# TKX90001_-_STRATASYS.net
KiCad netlist of a schematic drawn in EAGLE
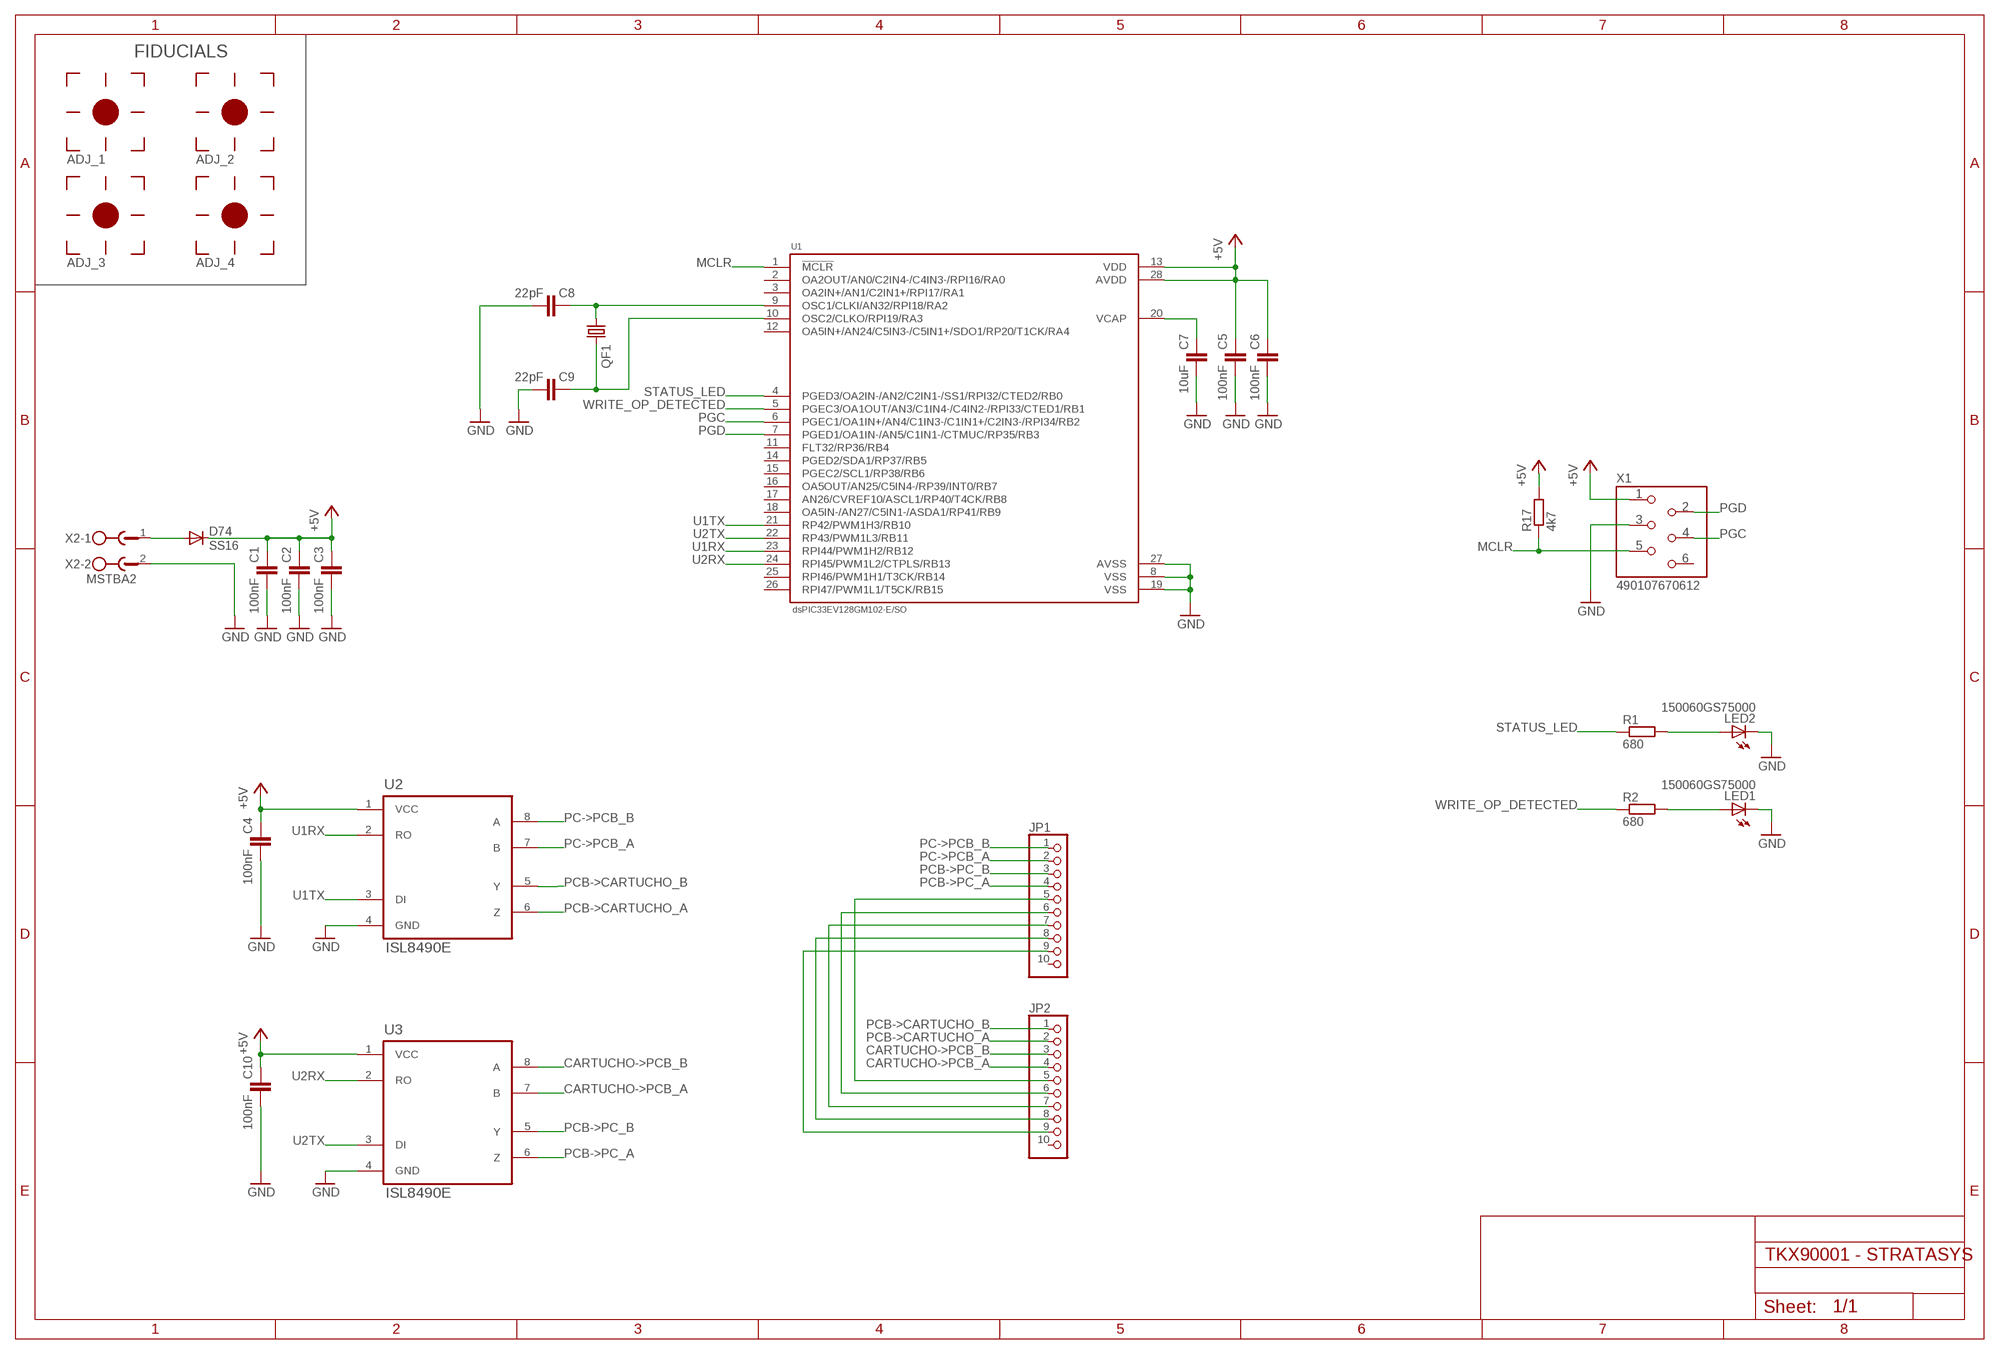
[diagram p0: schematic, sheet 1]

(export (version "E")
  (design (tool "Eeschema 10.0.6"))
  (components
    (comp (ref "ADJ_1")
      (value "FIDUCIAL")
      (footprint "eagle-import:FIDUCIAL")
      (libsource (lib "eagle-import") (part "FIDUCIAL"))
    )
    (comp (ref "ADJ_2")
      (value "FIDUCIAL")
      (footprint "eagle-import:FIDUCIAL")
      (libsource (lib "eagle-import") (part "FIDUCIAL"))
    )
    (comp (ref "ADJ_3")
      (value "FIDUCIAL")
      (footprint "eagle-import:FIDUCIAL")
      (libsource (lib "eagle-import") (part "FIDUCIAL"))
    )
    (comp (ref "ADJ_4")
      (value "FIDUCIAL")
      (footprint "eagle-import:FIDUCIAL")
      (libsource (lib "eagle-import") (part "FIDUCIAL"))
    )
    (comp (ref "C1")
      (value "100nF")
      (footprint "eagle-import:C0603K")
      (fields (field (name "PARTNO") "885012206020"))
      (libsource (lib "eagle-import") (part "C-EUC0603K"))
    )
    (comp (ref "C2")
      (value "100nF")
      (footprint "eagle-import:C0603K")
      (fields (field (name "PARTNO") "885012206020"))
      (libsource (lib "eagle-import") (part "C-EUC0603K"))
    )
    (comp (ref "C3")
      (value "100nF")
      (footprint "eagle-import:C0603K")
      (fields (field (name "PARTNO") "885012206020"))
      (libsource (lib "eagle-import") (part "C-EUC0603K"))
    )
    (comp (ref "C4")
      (value "100nF")
      (footprint "eagle-import:C0603K")
      (fields (field (name "PARTNO") "885012206020"))
      (libsource (lib "eagle-import") (part "C-EUC0603K"))
    )
    (comp (ref "C5")
      (value "100nF")
      (footprint "eagle-import:C0603K")
      (fields (field (name "PARTNO") "885012206020"))
      (libsource (lib "eagle-import") (part "C-EUC0603K"))
    )
    (comp (ref "C6")
      (value "100nF")
      (footprint "eagle-import:C0603K")
      (fields (field (name "PARTNO") "885012206020"))
      (libsource (lib "eagle-import") (part "C-EUC0603K"))
    )
    (comp (ref "C7")
      (value "10uF")
      (footprint "eagle-import:C1206K")
      (fields (field (name "PARTNO") "TAJA106K016RNJV"))
      (libsource (lib "eagle-import") (part "rcl_334_C-EUC1206K"))
    )
    (comp (ref "C8")
      (value "22pF")
      (footprint "eagle-import:C0603K")
      (fields (field (name "PARTNO") "C0603C220M4RACAUTO"))
      (libsource (lib "eagle-import") (part "rcl_334_C-EUC0603K"))
    )
    (comp (ref "C9")
      (value "22pF")
      (footprint "eagle-import:C0603K")
      (fields (field (name "PARTNO") "C0603C220M4RACAUTO"))
      (libsource (lib "eagle-import") (part "C-EUC0603K"))
    )
    (comp (ref "C10")
      (value "100nF")
      (footprint "eagle-import:C0603K")
      (fields (field (name "PARTNO") "885012206020"))
      (libsource (lib "eagle-import") (part "C-EUC0603K"))
    )
    (comp (ref "D74")
      (value "SS16")
      (footprint "eagle-import:SMB")
      (fields (field (name "PARTNO") "SS16T3G"))
      (libsource (lib "eagle-import") (part "DIODE-SMB"))
    )
    (comp (ref "JP1")
      (value "PINHD-1X10/90")
      (footprint "eagle-import:1X10_90")
      (libsource (lib "eagle-import") (part "PINHD-1X10/90"))
    )
    (comp (ref "JP2")
      (value "PINHD-1X10/90")
      (footprint "eagle-import:1X10_90")
      (libsource (lib "eagle-import") (part "PINHD-1X10/90"))
    )
    (comp (ref "LED1")
      (value "150060GS75000")
      (footprint "eagle-import:SML0603")
      (libsource (lib "eagle-import") (part "LEDSML0603"))
    )
    (comp (ref "LED2")
      (value "150060GS75000")
      (footprint "eagle-import:SML0603")
      (libsource (lib "eagle-import") (part "LEDSML0603"))
    )
    (comp (ref "QF1")
      (value "CRYSTALHC49S")
      (footprint "eagle-import:HC49_S")
      (libsource (lib "eagle-import") (part "CRYSTALHC49S"))
    )
    (comp (ref "R1")
      (value "680")
      (footprint "eagle-import:R0603")
      (fields (field (name "PARTNO") "RC0603FR-13680RL"))
      (libsource (lib "eagle-import") (part "R-EU_R0603"))
    )
    (comp (ref "R2")
      (value "680")
      (footprint "eagle-import:R0603")
      (fields (field (name "PARTNO") "RC0603FR-13680RL"))
      (libsource (lib "eagle-import") (part "R-EU_R0603"))
    )
    (comp (ref "R17")
      (value "4k7")
      (footprint "eagle-import:R0603")
      (fields (field (name "PARTNO") "RC0603FR-074K7L"))
      (libsource (lib "eagle-import") (part "R-EU_R0603"))
    )
    (comp (ref "U1")
      (value "dsPIC33EV128GM102-E/SO")
      (footprint "eagle-import:SOIC127P1028X256-28N")
      (fields (field (name "PARTNO") " dsPIC33EV128GM102-E/SO"))
      (libsource (lib "eagle-import") (part "DSPIC33EV128GM104-E/PT"))
    )
    (comp (ref "U2")
      (value "ISL8490E")
      (footprint "eagle-import:SOIC127P600X175-8N")
      (fields (field (name "PARTNO") "ISL8490EIBZ"))
      (libsource (lib "eagle-import") (part "ISL8490E"))
    )
    (comp (ref "U3")
      (value "ISL8490E")
      (footprint "eagle-import:SOIC127P600X175-8N")
      (fields (field (name "PARTNO") "ISL8490EIBZ"))
      (libsource (lib "eagle-import") (part "ISL8490E"))
    )
    (comp (ref "X1")
      (value "490107670612")
      (footprint "eagle-import:REDFIT_6POS")
      (libsource (lib "eagle-import") (part "REDFIT_6POS"))
    )
    (comp (ref "X2")
      (value "MSTBA2")
      (footprint "eagle-import:MSTBA2")
      (fields (field (name "MF") "FARNELL") (field (name "MPN") "1757242") (field (name "DNP") "T"))
      (libsource (lib "eagle-import") (part "MSTBA2"))
    )
  )
  (nets
    (net (code "1") (name "+5V") (class "Default")
      (node (ref "C1") (pin "1") (pinfunction "1_1") (pintype "passive"))
      (node (ref "C10") (pin "1") (pinfunction "1_1") (pintype "passive"))
      (node (ref "C2") (pin "1") (pinfunction "1_1") (pintype "passive"))
      (node (ref "C3") (pin "1") (pinfunction "1_1") (pintype "passive"))
      (node (ref "C4") (pin "1") (pinfunction "1_1") (pintype "passive"))
      (node (ref "C5") (pin "1") (pinfunction "1_1") (pintype "passive"))
      (node (ref "C6") (pin "1") (pinfunction "1_1") (pintype "passive"))
      (node (ref "D74") (pin "C") (pinfunction "C_C") (pintype "passive"))
      (node (ref "R17") (pin "2") (pinfunction "2_2") (pintype "passive"))
      (node (ref "U1") (pin "13") (pinfunction "VDD_13") (pintype "power_in"))
      (node (ref "U1") (pin "28") (pinfunction "AVDD_28") (pintype "bidirectional"))
      (node (ref "U2") (pin "1") (pinfunction "VCC_1") (pintype "power_in"))
      (node (ref "U3") (pin "1") (pinfunction "VCC_1") (pintype "power_in"))
      (node (ref "X1") (pin "P$1") (pinfunction "P$1_P$1") (pintype "bidirectional"))
    )
    (net (code "2") (name "/CARTUCHO->PCB_A") (class "Default")
      (node (ref "JP2") (pin "4") (pinfunction "4_4") (pintype "passive"))
      (node (ref "U3") (pin "7") (pinfunction "B_7") (pintype "input"))
    )
    (net (code "3") (name "/CARTUCHO->PCB_B") (class "Default")
      (node (ref "JP2") (pin "3") (pinfunction "3_3") (pintype "passive"))
      (node (ref "U3") (pin "8") (pinfunction "A_8") (pintype "input"))
    )
    (net (code "4") (name "/MCLR") (class "Default")
      (node (ref "R17") (pin "1") (pinfunction "1_1") (pintype "passive"))
      (node (ref "U1") (pin "1") (pinfunction "~{MCLR}_1") (pintype "input"))
      (node (ref "X1") (pin "P$5") (pinfunction "P$5_P$5") (pintype "bidirectional"))
    )
    (net (code "5") (name "/PC->PCB_A") (class "Default")
      (node (ref "JP1") (pin "2") (pinfunction "2_2") (pintype "passive"))
      (node (ref "U2") (pin "7") (pinfunction "B_7") (pintype "input"))
    )
    (net (code "6") (name "/PC->PCB_B") (class "Default")
      (node (ref "JP1") (pin "1") (pinfunction "1_1") (pintype "passive"))
      (node (ref "U2") (pin "8") (pinfunction "A_8") (pintype "input"))
    )
    (net (code "7") (name "/PCB->CARTUCHO_A") (class "Default")
      (node (ref "JP2") (pin "2") (pinfunction "2_2") (pintype "passive"))
      (node (ref "U2") (pin "6") (pinfunction "Z_6") (pintype "output"))
    )
    (net (code "8") (name "/PCB->CARTUCHO_B") (class "Default")
      (node (ref "JP2") (pin "1") (pinfunction "1_1") (pintype "passive"))
      (node (ref "U2") (pin "5") (pinfunction "Y_5") (pintype "output"))
    )
    (net (code "9") (name "/PCB->PC_A") (class "Default")
      (node (ref "JP1") (pin "4") (pinfunction "4_4") (pintype "passive"))
      (node (ref "U3") (pin "6") (pinfunction "Z_6") (pintype "output"))
    )
    (net (code "10") (name "/PCB->PC_B") (class "Default")
      (node (ref "JP1") (pin "3") (pinfunction "3_3") (pintype "passive"))
      (node (ref "U3") (pin "5") (pinfunction "Y_5") (pintype "output"))
    )
    (net (code "11") (name "/PGC") (class "Default")
      (node (ref "U1") (pin "6") (pinfunction "PGEC1/OA1IN+/AN4/C1IN3-/C1IN1+/C2IN3-/RPI34/RB2_6") (pintype "bidirectional"))
      (node (ref "X1") (pin "P$4") (pinfunction "P$4_P$4") (pintype "bidirectional"))
    )
    (net (code "12") (name "/PGD") (class "Default")
      (node (ref "U1") (pin "7") (pinfunction "PGED1/OA1IN-/AN5/C1IN1-/CTMUC/RP35/RB3_7") (pintype "bidirectional"))
      (node (ref "X1") (pin "P$2") (pinfunction "P$2_P$2") (pintype "bidirectional"))
    )
    (net (code "13") (name "/STATUS_LED") (class "Default")
      (node (ref "R1") (pin "1") (pinfunction "1_1") (pintype "passive"))
      (node (ref "U1") (pin "4") (pinfunction "PGED3/OA2IN-/AN2/C2IN1-/SS1/RPI32/CTED2/RB0_4") (pintype "bidirectional"))
    )
    (net (code "14") (name "/U1RX") (class "Default")
      (node (ref "U1") (pin "23") (pinfunction "RPI44/PWM1H2/RB12_23") (pintype "bidirectional"))
      (node (ref "U2") (pin "2") (pinfunction "RO_2") (pintype "output"))
    )
    (net (code "15") (name "/U1TX") (class "Default")
      (node (ref "U1") (pin "21") (pinfunction "RP42/PWM1H3/RB10_21") (pintype "bidirectional"))
      (node (ref "U2") (pin "3") (pinfunction "DI_3") (pintype "input"))
    )
    (net (code "16") (name "/U2RX") (class "Default")
      (node (ref "U1") (pin "24") (pinfunction "RPI45/PWM1L2/CTPLS/RB13_24") (pintype "bidirectional"))
      (node (ref "U3") (pin "2") (pinfunction "RO_2") (pintype "output"))
    )
    (net (code "17") (name "/U2TX") (class "Default")
      (node (ref "U1") (pin "22") (pinfunction "RP43/PWM1L3/RB11_22") (pintype "bidirectional"))
      (node (ref "U3") (pin "3") (pinfunction "DI_3") (pintype "input"))
    )
    (net (code "18") (name "/WRITE_OP_DETECTED") (class "Default")
      (node (ref "R2") (pin "1") (pinfunction "1_1") (pintype "passive"))
      (node (ref "U1") (pin "5") (pinfunction "PGEC3/OA1OUT/AN3/C1IN4-/C4IN2-/RPI33/CTED1/RB1_5") (pintype "bidirectional"))
    )
    (net (code "19") (name "GND") (class "Default")
      (node (ref "C1") (pin "2") (pinfunction "2_2") (pintype "passive"))
      (node (ref "C10") (pin "2") (pinfunction "2_2") (pintype "passive"))
      (node (ref "C2") (pin "2") (pinfunction "2_2") (pintype "passive"))
      (node (ref "C3") (pin "2") (pinfunction "2_2") (pintype "passive"))
      (node (ref "C4") (pin "2") (pinfunction "2_2") (pintype "passive"))
      (node (ref "C5") (pin "2") (pinfunction "2_2") (pintype "passive"))
      (node (ref "C6") (pin "2") (pinfunction "2_2") (pintype "passive"))
      (node (ref "C7") (pin "2") (pinfunction "2_2") (pintype "passive"))
      (node (ref "C8") (pin "2") (pinfunction "2_2") (pintype "passive"))
      (node (ref "C9") (pin "2") (pinfunction "2_2") (pintype "passive"))
      (node (ref "LED1") (pin "C") (pinfunction "C_C") (pintype "passive"))
      (node (ref "LED2") (pin "C") (pinfunction "C_C") (pintype "passive"))
      (node (ref "U1") (pin "19") (pinfunction "VSS_19") (pintype "power_in"))
      (node (ref "U1") (pin "27") (pinfunction "AVSS_27") (pintype "bidirectional"))
      (node (ref "U1") (pin "8") (pinfunction "VSS_8") (pintype "power_in"))
      (node (ref "U2") (pin "4") (pinfunction "GND_4") (pintype "passive"))
      (node (ref "U3") (pin "4") (pinfunction "GND_4") (pintype "passive"))
      (node (ref "X1") (pin "P$3") (pinfunction "P$3_P$3") (pintype "bidirectional"))
      (node (ref "X2") (pin "2") (pinfunction "1_2") (pintype "passive"))
    )
    (net (code "20") (name "Net-(D74-PadA)") (class "Default")
      (node (ref "D74") (pin "A") (pinfunction "A_A") (pintype "passive"))
      (node (ref "X2") (pin "1") (pinfunction "1_1") (pintype "passive"))
    )
    (net (code "21") (name "Net-(JP1-Pad5)") (class "Default")
      (node (ref "JP1") (pin "5") (pinfunction "5_5") (pintype "passive"))
      (node (ref "JP2") (pin "5") (pinfunction "5_5") (pintype "passive"))
    )
    (net (code "22") (name "Net-(JP1-Pad6)") (class "Default")
      (node (ref "JP1") (pin "6") (pinfunction "6_6") (pintype "passive"))
      (node (ref "JP2") (pin "6") (pinfunction "6_6") (pintype "passive"))
    )
    (net (code "23") (name "Net-(JP1-Pad7)") (class "Default")
      (node (ref "JP1") (pin "7") (pinfunction "7_7") (pintype "passive"))
      (node (ref "JP2") (pin "7") (pinfunction "7_7") (pintype "passive"))
    )
    (net (code "24") (name "Net-(JP1-Pad8)") (class "Default")
      (node (ref "JP1") (pin "8") (pinfunction "8_8") (pintype "passive"))
      (node (ref "JP2") (pin "8") (pinfunction "8_8") (pintype "passive"))
    )
    (net (code "25") (name "Net-(JP1-Pad9)") (class "Default")
      (node (ref "JP1") (pin "9") (pinfunction "9_9") (pintype "passive"))
      (node (ref "JP2") (pin "9") (pinfunction "9_9") (pintype "passive"))
    )
    (net (code "26") (name "Net-(LED1-PadA)") (class "Default")
      (node (ref "LED1") (pin "A") (pinfunction "A_A") (pintype "passive"))
      (node (ref "R2") (pin "2") (pinfunction "2_2") (pintype "passive"))
    )
    (net (code "27") (name "Net-(LED2-PadA)") (class "Default")
      (node (ref "LED2") (pin "A") (pinfunction "A_A") (pintype "passive"))
      (node (ref "R1") (pin "2") (pinfunction "2_2") (pintype "passive"))
    )
    (net (code "28") (name "Net-(U1-OSC1{slash}CLKI{slash}AN32{slash}RPI18{slash}RA2)") (class "Default")
      (node (ref "C8") (pin "1") (pinfunction "1_1") (pintype "passive"))
      (node (ref "QF1") (pin "1") (pinfunction "1_1") (pintype "passive"))
      (node (ref "U1") (pin "9") (pinfunction "OSC1/CLKI/AN32/RPI18/RA2_9") (pintype "bidirectional"))
    )
    (net (code "29") (name "Net-(U1-OSC2{slash}CLKO{slash}RPI19{slash}RA3)") (class "Default")
      (node (ref "C9") (pin "1") (pinfunction "1_1") (pintype "passive"))
      (node (ref "QF1") (pin "2") (pinfunction "2_2") (pintype "passive"))
      (node (ref "U1") (pin "10") (pinfunction "OSC2/CLKO/RPI19/RA3_10") (pintype "bidirectional"))
    )
    (net (code "30") (name "Net-(U1-VCAP)") (class "Default")
      (node (ref "C7") (pin "1") (pinfunction "1_1") (pintype "passive"))
      (node (ref "U1") (pin "20") (pinfunction "VCAP_20") (pintype "power_in"))
    )
    (net (code "31") (name "unconnected-(JP1-Pad10)") (class "Default")
      (node (ref "JP1") (pin "10") (pinfunction "10_10") (pintype "passive"))
    )
    (net (code "32") (name "unconnected-(JP2-Pad10)") (class "Default")
      (node (ref "JP2") (pin "10") (pinfunction "10_10") (pintype "passive"))
    )
    (net (code "33") (name "unconnected-(U1-AN26{slash}CVREF10{slash}ASCL1{slash}RP40{slash}T4CK{slash}RB8-Pad17)") (class "Default")
      (node (ref "U1") (pin "17") (pinfunction "AN26/CVREF10/ASCL1/RP40/T4CK/RB8_17") (pintype "bidirectional"))
    )
    (net (code "34") (name "unconnected-(U1-FLT32{slash}RP36{slash}RB4-Pad11)") (class "Default")
      (node (ref "U1") (pin "11") (pinfunction "FLT32/RP36/RB4_11") (pintype "bidirectional"))
    )
    (net (code "35") (name "unconnected-(U1-OA2IN+{slash}AN1{slash}C2IN1+{slash}RPI17{slash}RA1-Pad3)") (class "Default")
      (node (ref "U1") (pin "3") (pinfunction "OA2IN+/AN1/C2IN1+/RPI17/RA1_3") (pintype "bidirectional"))
    )
    (net (code "36") (name "unconnected-(U1-OA2OUT{slash}AN0{slash}C2IN4-{slash}C4IN3-{slash}RPI16{slash}RA0-Pad2)") (class "Default")
      (node (ref "U1") (pin "2") (pinfunction "OA2OUT/AN0/C2IN4-/C4IN3-/RPI16/RA0_2") (pintype "bidirectional"))
    )
    (net (code "37") (name "unconnected-(U1-OA5IN+{slash}AN24{slash}C5IN3-{slash}C5IN1+{slash}SDO1{slash}RP20{slash}T1CK{slash}RA4-Pad12)") (class "Default")
      (node (ref "U1") (pin "12") (pinfunction "OA5IN+/AN24/C5IN3-/C5IN1+/SDO1/RP20/T1CK/RA4_12") (pintype "bidirectional"))
    )
    (net (code "38") (name "unconnected-(U1-OA5IN-{slash}AN27{slash}C5IN1-{slash}ASDA1{slash}RP41{slash}RB9-Pad18)") (class "Default")
      (node (ref "U1") (pin "18") (pinfunction "OA5IN-/AN27/C5IN1-/ASDA1/RP41/RB9_18") (pintype "bidirectional"))
    )
    (net (code "39") (name "unconnected-(U1-OA5OUT{slash}AN25{slash}C5IN4-{slash}RP39{slash}INT0{slash}RB7-Pad16)") (class "Default")
      (node (ref "U1") (pin "16") (pinfunction "OA5OUT/AN25/C5IN4-/RP39/INT0/RB7_16") (pintype "bidirectional"))
    )
    (net (code "40") (name "unconnected-(U1-PGEC2{slash}SCL1{slash}RP38{slash}RB6-Pad15)") (class "Default")
      (node (ref "U1") (pin "15") (pinfunction "PGEC2/SCL1/RP38/RB6_15") (pintype "bidirectional"))
    )
    (net (code "41") (name "unconnected-(U1-PGED2{slash}SDA1{slash}RP37{slash}RB5-Pad14)") (class "Default")
      (node (ref "U1") (pin "14") (pinfunction "PGED2/SDA1/RP37/RB5_14") (pintype "bidirectional"))
    )
    (net (code "42") (name "unconnected-(U1-RPI46{slash}PWM1H1{slash}T3CK{slash}RB14-Pad25)") (class "Default")
      (node (ref "U1") (pin "25") (pinfunction "RPI46/PWM1H1/T3CK/RB14_25") (pintype "bidirectional"))
    )
    (net (code "43") (name "unconnected-(U1-RPI47{slash}PWM1L1{slash}T5CK{slash}RB15-Pad26)") (class "Default")
      (node (ref "U1") (pin "26") (pinfunction "RPI47/PWM1L1/T5CK/RB15_26") (pintype "bidirectional"))
    )
    (net (code "44") (name "unconnected-(X1-PadP$6)") (class "Default")
      (node (ref "X1") (pin "P$6") (pinfunction "P$6_P$6") (pintype "bidirectional"))
    )
  )
)
